# 08-USB.net
KiCad netlist of a schematic drawn in Altium Designer
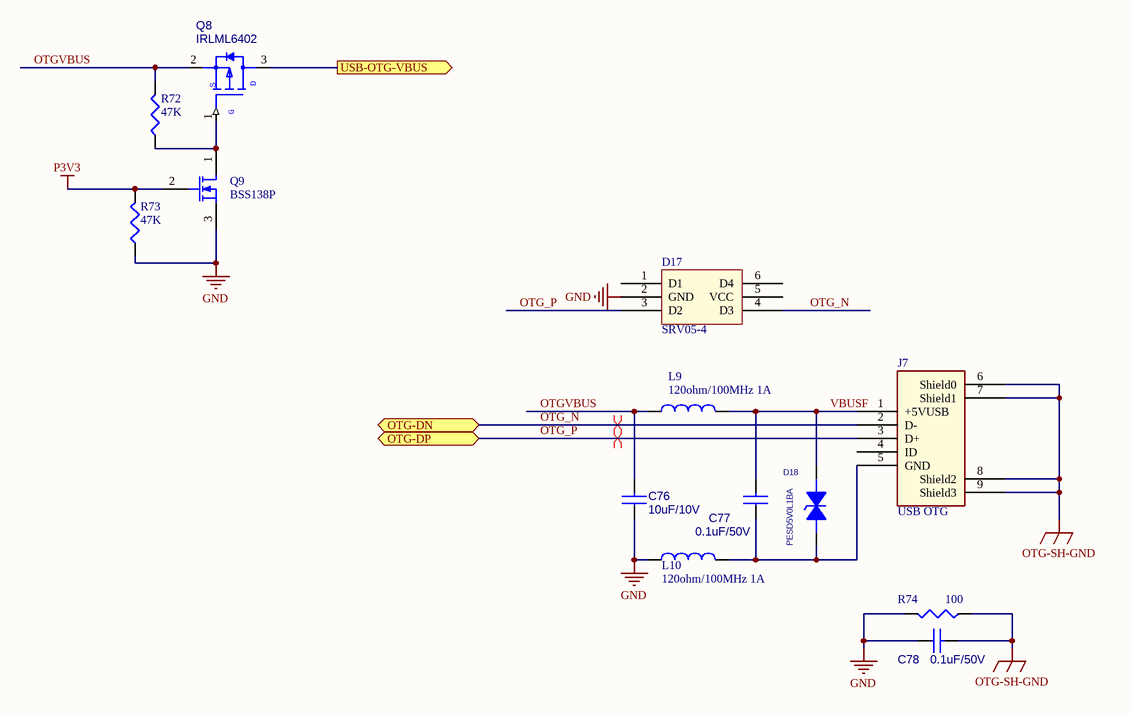
[diagram p0: 08-USB.SchDoc]

(export (version "E")
  (design (tool "Eeschema 10.0.6"))
  (components
    (comp (ref "C76") (value "10uF/10V") (libsource (lib "*") (part "CAP_Dup1")))
    (comp (ref "C77") (value "0.1uF/50V") (libsource (lib "*") (part "CAP_Dup1")))
    (comp (ref "C78") (value "0.1uF/50V") (libsource (lib "*") (part "CAP_Dup1")))
    (comp (ref "D17") (value "SRV05-4") (footprint "SOT23-6") (libsource (lib "Schlib") (part "SRV05-4")))
    (comp (ref "D18") (value "PESD5V0L1BA") (libsource (lib "*") (part "PESD")))
    (comp (ref "J7")
      (value "USB OTG")
      (footprint "MINIUSB-TYPEAB")
      (fields (field (name "PART NUMBER") "SP063100800"))
      (libsource (lib "*") (part "FOX_UH51543-JS7"))
    )
    (comp (ref "L9")
      (value "120ohm/100MHz 1A")
      (footprint "0603")
      (description "Inductor")
      (fields (field (name "PUBLISHER") "Altium Limited"))
      (libsource (lib "Miscellaneous Devices") (part "Inductor"))
    )
    (comp (ref "L10")
      (value "120ohm/100MHz 1A")
      (footprint "0603")
      (description "Inductor")
      (fields (field (name "PUBLISHER") "Altium Limited"))
      (libsource (lib "Miscellaneous Devices") (part "Inductor"))
    )
    (comp (ref "Q8")
      (value "IRLML6402")
      (footprint "MOSFET")
      (fields (field (name "PART NUMBER") "SB934010010"))
      (libsource (lib "*") (part "AO3401L_SOT23-3_0"))
    )
    (comp (ref "Q9")
      (value "BSS138P")
      (footprint "NPN")
      (description "N-Channel MOSFET")
      (fields (field (name "PUBLISHER") "Altium Limited"))
      (libsource (lib "Miscellaneous Devices") (part "MOSFET-N"))
    )
    (comp (ref "R72") (value "47K") (footprint "0402") (libsource (lib "*") (part "CR16-1003FM")))
    (comp (ref "R73") (value "47K") (footprint "0402") (libsource (lib "*") (part "CR16-1003FM")))
    (comp (ref "R74") (value "100") (footprint "0402") (libsource (lib "*") (part "CR16-1003FM")))
  )
  (nets
    (net (code "1") (name "/OTGVBUS") (class "Default")
      (node (ref "C76") (pin "2") (pinfunction "2_2") (pintype "passive"))
      (node (ref "L9") (pin "1") (pinfunction "1_1") (pintype "passive"))
      (node (ref "Q8") (pin "2") (pinfunction "S_2") (pintype "passive"))
      (node (ref "R72") (pin "2") (pinfunction "2_2") (pintype "passive"))
    )
    (net (code "2") (name "/OTG_N") (class "Default")
      (node (ref "D17") (pin "4") (pinfunction "D3_4") (pintype "passive"))
      (node (ref "J7") (pin "2") (pinfunction "D-_2") (pintype "passive"))
    )
    (net (code "3") (name "/OTG_P") (class "Default")
      (node (ref "D17") (pin "3") (pinfunction "D2_3") (pintype "passive"))
      (node (ref "J7") (pin "3") (pinfunction "D+_3") (pintype "passive"))
    )
    (net (code "4") (name "/USB-OTG-VBUS") (class "Default")
      (node (ref "Q8") (pin "3") (pinfunction "D_3") (pintype "passive"))
    )
    (net (code "5") (name "/VBUSF") (class "Default")
      (node (ref "C77") (pin "2") (pinfunction "2_2") (pintype "passive"))
      (node (ref "D18") (pin "2") (pinfunction "2_2") (pintype "passive"))
      (node (ref "J7") (pin "1") (pinfunction "+5VUSB_1") (pintype "passive"))
      (node (ref "L9") (pin "2") (pinfunction "2_2") (pintype "passive"))
    )
    (net (code "6") (name "GND") (class "Default")
      (node (ref "C76") (pin "1") (pinfunction "1_1") (pintype "passive"))
      (node (ref "C78") (pin "1") (pinfunction "1_1") (pintype "passive"))
      (node (ref "D17") (pin "2") (pinfunction "GND_2") (pintype "passive"))
      (node (ref "L10") (pin "1") (pinfunction "1_1") (pintype "passive"))
      (node (ref "Q9") (pin "3") (pinfunction "S_3") (pintype "passive"))
      (node (ref "R73") (pin "1") (pinfunction "1_1") (pintype "passive"))
      (node (ref "R74") (pin "2") (pinfunction "2_2") (pintype "passive"))
    )
    (net (code "7") (name "Net-(J7-GND)") (class "Default")
      (node (ref "C77") (pin "1") (pinfunction "1_1") (pintype "passive"))
      (node (ref "D18") (pin "1") (pinfunction "1_1") (pintype "passive"))
      (node (ref "J7") (pin "5") (pinfunction "GND_5") (pintype "passive"))
      (node (ref "L10") (pin "2") (pinfunction "2_2") (pintype "passive"))
    )
    (net (code "8") (name "Net-(Q8-G)") (class "Default")
      (node (ref "Q8") (pin "1") (pinfunction "G_1") (pintype "input"))
      (node (ref "Q9") (pin "1") (pinfunction "D_1") (pintype "passive"))
      (node (ref "R72") (pin "1") (pinfunction "1_1") (pintype "passive"))
    )
    (net (code "9") (name "OTG-SH-GND") (class "Default")
      (node (ref "C78") (pin "2") (pinfunction "2_2") (pintype "passive"))
      (node (ref "J7") (pin "6") (pinfunction "Shield0_6") (pintype "passive"))
      (node (ref "J7") (pin "7") (pinfunction "Shield1_7") (pintype "passive"))
      (node (ref "J7") (pin "8") (pinfunction "Shield2_8") (pintype "passive"))
      (node (ref "J7") (pin "9") (pinfunction "Shield3_9") (pintype "passive"))
      (node (ref "R74") (pin "1") (pinfunction "1_1") (pintype "passive"))
    )
    (net (code "10") (name "P3V3") (class "Default")
      (node (ref "Q9") (pin "2") (pinfunction "G_2") (pintype "passive"))
      (node (ref "R73") (pin "2") (pinfunction "2_2") (pintype "passive"))
    )
    (net (code "11") (name "unconnected-(D17-D1-Pad1)") (class "Default")
      (node (ref "D17") (pin "1") (pinfunction "D1_1") (pintype "passive"))
    )
    (net (code "12") (name "unconnected-(D17-D4-Pad6)") (class "Default")
      (node (ref "D17") (pin "6") (pinfunction "D4_6") (pintype "passive"))
    )
    (net (code "13") (name "unconnected-(D17-VCC-Pad5)") (class "Default")
      (node (ref "D17") (pin "5") (pinfunction "VCC_5") (pintype "passive"))
    )
    (net (code "14") (name "unconnected-(J7-ID-Pad4)") (class "Default")
      (node (ref "J7") (pin "4") (pinfunction "ID_4") (pintype "passive"))
    )
  )
)
